# charger.net
KiCad netlist of a schematic drawn in Altium Designer
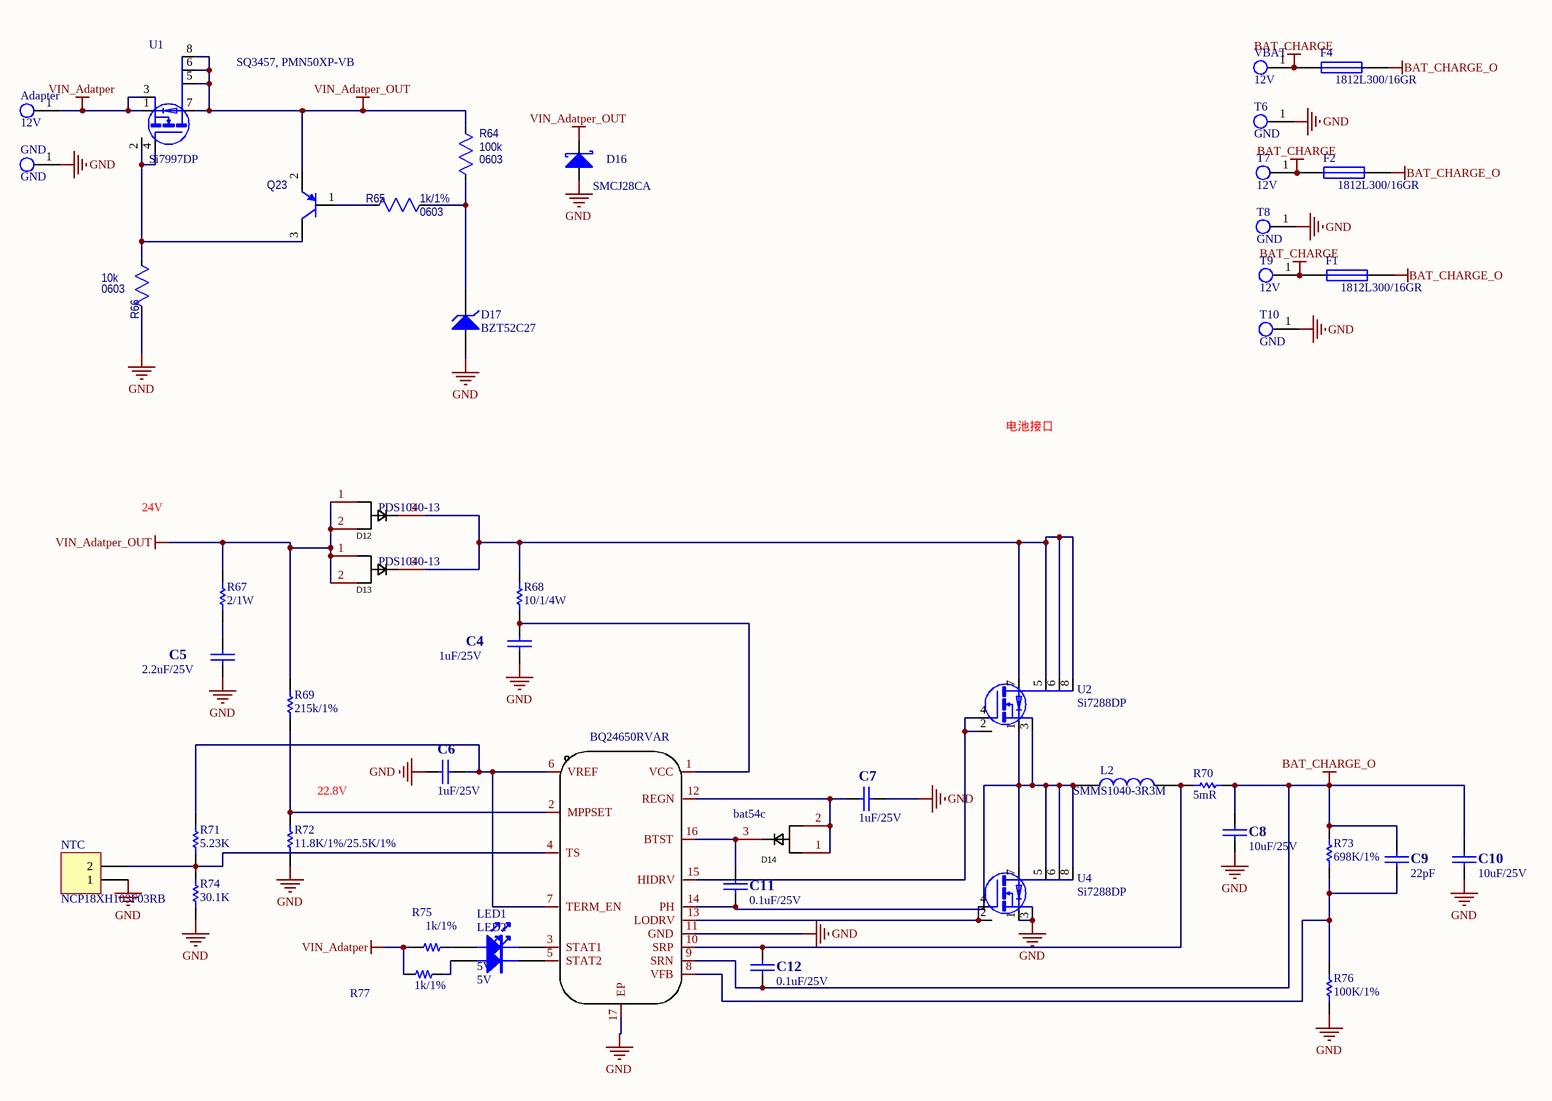
[diagram p0: charger.SchDoc]

(export (version "E")
  (design (tool "Eeschema 10.0.6"))
  (components
    (comp (ref "Adapter") (value "12V") (footprint "FIX-4.5") (libsource (lib "Schlib_20110825") (part "TP")))
    (comp (ref "C4")
      (value "1uF/25V")
      (footprint "0805C")
      (description "Capacitor")
      (libsource (lib "*") (part "CAP"))
    )
    (comp (ref "C5")
      (value "2.2uF/25V")
      (footprint "1210C")
      (description "Capacitor")
      (libsource (lib "*") (part "CAP"))
    )
    (comp (ref "C6")
      (value "1uF/25V")
      (footprint "0603C")
      (description "Capacitor")
      (libsource (lib "*") (part "CAP"))
    )
    (comp (ref "C7")
      (value "1uF/25V")
      (footprint "0603C")
      (description "Capacitor")
      (libsource (lib "*") (part "CAP"))
    )
    (comp (ref "C8")
      (value "10uF/25V")
      (footprint "0603C")
      (description "Capacitor")
      (libsource (lib "*") (part "CAP"))
    )
    (comp (ref "C9")
      (value "22pF")
      (footprint "0603C")
      (description "Capacitor")
      (libsource (lib "*") (part "CAP"))
    )
    (comp (ref "C10")
      (value "10uF/25V")
      (footprint "0603C")
      (description "Capacitor")
      (libsource (lib "*") (part "CAP"))
    )
    (comp (ref "C11")
      (value "0.1uF/25V")
      (footprint "0603C")
      (description "Capacitor")
      (libsource (lib "*") (part "CAP"))
    )
    (comp (ref "C12")
      (value "0.1uF/25V")
      (footprint "0603C")
      (description "Capacitor")
      (libsource (lib "*") (part "CAP"))
    )
    (comp (ref "D12")
      (value "PDS1040-13")
      (footprint "POWERDI-5_L5.4-W4.0-LS6.5-RD")
      (fields (field (name "MANUFACTURER") "DIODES(美台)"))
      (libsource (lib "Schlib_20110825") (part "PDS1040-13"))
    )
    (comp (ref "D13")
      (value "PDS1040-13")
      (footprint "POWERDI-5_L5.4-W4.0-LS6.5-RD")
      (fields (field (name "MANUFACTURER") "DIODES(美台)"))
      (libsource (lib "Schlib_20110825") (part "PDS1040-13"))
    )
    (comp (ref "D14")
      (value "bat54c")
      (footprint "sot23-3")
      (fields (field (name "MANUFACTURER") "DIODES(美台)") (field (name "MANUFACTURER PART") "PDS1040-13"))
      (libsource (lib "Schlib_20110825") (part "PDS1040-13"))
    )
    (comp (ref "D16")
      (value "SMCJ28CA")
      (footprint "SMC")
      (description "Schottky Diode")
      (libsource (lib "*") (part "DIODE S"))
    )
    (comp (ref "D17")
      (value "BZT52C27")
      (footprint "sod123")
      (libsource (lib "Bogen") (part "BZT52C12S-7-F"))
    )
    (comp (ref "F1")
      (value "1812L300/16GR")
      (footprint "1812-F")
      (description "Fuse")
      (fields (field (name "PUBLISHER") "Altium Limited"))
      (libsource (lib "Miscellaneous Devices") (part "Fuse 1"))
    )
    (comp (ref "F2")
      (value "1812L300/16GR")
      (footprint "1812-F")
      (description "Fuse")
      (fields (field (name "PUBLISHER") "Altium Limited"))
      (libsource (lib "Miscellaneous Devices") (part "Fuse 1"))
    )
    (comp (ref "F4")
      (value "1812L300/16GR")
      (footprint "1812-F")
      (description "Fuse")
      (fields (field (name "PUBLISHER") "Altium Limited"))
      (libsource (lib "Miscellaneous Devices") (part "Fuse 1"))
    )
    (comp (ref "GND") (value "GND") (footprint "FIX-4.5") (libsource (lib "Schlib_20110825") (part "TP")))
    (comp (ref "L2") (value "SMMS1040-3R3M") (footprint "MSS1038") (libsource (lib "*") (part "INDUCTOR")))
    (comp (ref "LED1") (value "5V") (footprint "0603LED") (libsource (lib "*") (part "LED")))
    (comp (ref "LED2") (value "5V") (footprint "0603LED") (libsource (lib "*") (part "LED")))
    (comp (ref "NTC")
      (value "NCP18XH103F03RB")
      (footprint "HDR1X2")
      (description "XH2.54 2P 立贴")
      (fields (field (name "PUBLISHER") "Altium Limited"))
      (libsource (lib "Miscellaneous Connectors") (part "Header 2"))
    )
    (comp (ref "Q23")
      (value "MMBT4403-7-F")
      (footprint "SOT23-3")
      (libsource (lib "Karl") (part "OEM_Diodes_MMBT4403"))
    )
    (comp (ref "R64")
      (value "100k")
      (footprint "RESC1608X055N_0603")
      (fields
        (field (name "PARTNUMBER") "RC0603FR-0716K9L")
        (field (name "TOLERANCE") "tol")
        (field (name "PACKAGE") "0603")
      )
      (libsource (lib "Karl") (part "Resistor_0603"))
    )
    (comp (ref "R65")
      (value "1k/1%")
      (footprint "RESC1608X055N_0603")
      (fields
        (field (name "PARTNUMBER") "RC0603FR-071KL")
        (field (name "TOLERANCE") "tol")
        (field (name "PACKAGE") "0603")
      )
      (libsource (lib "Karl") (part "Resistor_0603"))
    )
    (comp (ref "R66")
      (value "10k")
      (footprint "RESC1608X055N_0603")
      (fields
        (field (name "PARTNUMBER") "RC0603FR-071KL")
        (field (name "TOLERANCE") "tol")
        (field (name "PACKAGE") "0603")
      )
      (libsource (lib "Karl") (part "Resistor_0603"))
    )
    (comp (ref "R67")
      (value "2/1W")
      (footprint "2512R")
      (description "Resistor")
      (fields (field (name "PUBLISHER") "Altium Limited"))
      (libsource (lib "Miscellaneous Devices") (part "Res1"))
    )
    (comp (ref "R68")
      (value "10/1/4W")
      (footprint "1206R")
      (description "Resistor")
      (fields (field (name "PUBLISHER") "Altium Limited"))
      (libsource (lib "Miscellaneous Devices") (part "Res1"))
    )
    (comp (ref "R69")
      (value "215k/1%")
      (footprint "0603R")
      (description "Resistor")
      (fields (field (name "PUBLISHER") "Altium Limited"))
      (libsource (lib "Miscellaneous Devices") (part "Res1"))
    )
    (comp (ref "R70")
      (value "5mR")
      (footprint "2512R")
      (description "Resistor")
      (fields (field (name "PUBLISHER") "Altium Limited"))
      (libsource (lib "Miscellaneous Devices") (part "Res1"))
    )
    (comp (ref "R71")
      (value "5.23K")
      (footprint "0603R")
      (description "Resistor")
      (fields (field (name "PUBLISHER") "Altium Limited"))
      (libsource (lib "Miscellaneous Devices") (part "Res1"))
    )
    (comp (ref "R72")
      (value "11.8K/1%/25.5K/1%")
      (footprint "0603R")
      (description "Resistor")
      (fields (field (name "PUBLISHER") "Altium Limited"))
      (libsource (lib "Miscellaneous Devices") (part "Res1"))
    )
    (comp (ref "R73")
      (value "698K/1%")
      (footprint "0603R")
      (description "Resistor")
      (fields (field (name "PUBLISHER") "Altium Limited"))
      (libsource (lib "Miscellaneous Devices") (part "Res1"))
    )
    (comp (ref "R74")
      (value "30.1K")
      (footprint "0603R")
      (description "Resistor")
      (fields (field (name "PUBLISHER") "Altium Limited"))
      (libsource (lib "Miscellaneous Devices") (part "Res1"))
    )
    (comp (ref "R75") (value "1k/1%") (footprint "0603R") (libsource (lib "JRJ_1") (part "R")))
    (comp (ref "R76")
      (value "100K/1%")
      (footprint "0603R")
      (description "Resistor")
      (fields (field (name "PUBLISHER") "Altium Limited"))
      (libsource (lib "Miscellaneous Devices") (part "Res1"))
    )
    (comp (ref "R77") (value "1k/1%") (footprint "0603R") (libsource (lib "JRJ_1") (part "R")))
    (comp (ref "T6") (value "GND") (footprint "FIX-4.5") (libsource (lib "Schlib_20110825") (part "TP")))
    (comp (ref "T7") (value "12V") (footprint "FIX-4.5") (libsource (lib "Schlib_20110825") (part "TP")))
    (comp (ref "T8") (value "GND") (footprint "FIX-4.5") (libsource (lib "Schlib_20110825") (part "TP")))
    (comp (ref "T9") (value "12V") (footprint "FIX-4.5") (libsource (lib "Schlib_20110825") (part "TP")))
    (comp (ref "T10") (value "GND") (footprint "FIX-4.5") (libsource (lib "Schlib_20110825") (part "TP")))
    (comp (ref "U1")
      (value "Si7997DP")
      (footprint "PowerPAK SO-8")
      (description "Sia430DJ")
      (libsource (lib "Schlib_20110825") (part "Si7997DP"))
    )
    (comp (ref "U2")
      (value "Si7288DP")
      (footprint "PowerPAK SO-8")
      (description "Sia430DJ")
      (libsource (lib "Schlib_20110825") (part "Si7997DP"))
    )
    (comp (ref "U4")
      (value "Si7288DP")
      (footprint "PowerPAK SO-8")
      (description "Sia430DJ")
      (libsource (lib "Schlib_20110825") (part "Si7997DP"))
    )
    (comp (ref "U5")
      (value "BQ24650RVAR")
      (footprint "VQFN-16_L3.6-W3.6-P0.50-BL-EP")
      (fields (field (name "MANUFACTURER") "TI(德州仪器)"))
      (libsource (lib "Schlib_20110825") (part "BQ24650RVAR"))
    )
    (comp (ref "VBAT") (value "12V") (footprint "FIX-4.5") (libsource (lib "Schlib_20110825") (part "TP")))
  )
  (nets
    (net (code "1") (name "BAT_CHARGE") (class "Default")
      (node (ref "F1") (pin "1") (pinfunction "1_1") (pintype "passive"))
      (node (ref "F2") (pin "1") (pinfunction "1_1") (pintype "passive"))
      (node (ref "F4") (pin "1") (pinfunction "1_1") (pintype "passive"))
      (node (ref "T7") (pin "1") (pintype "passive"))
      (node (ref "T9") (pin "1") (pintype "passive"))
      (node (ref "VBAT") (pin "1") (pintype "passive"))
    )
    (net (code "2") (name "BAT_CHARGE_O") (class "Default")
      (node (ref "C10") (pin "2") (pinfunction "2_2") (pintype "passive"))
      (node (ref "C12") (pin "1") (pinfunction "1_1") (pintype "passive"))
      (node (ref "C8") (pin "2") (pinfunction "2_2") (pintype "passive"))
      (node (ref "C9") (pin "2") (pinfunction "2_2") (pintype "passive"))
      (node (ref "F1") (pin "2") (pinfunction "2_2") (pintype "passive"))
      (node (ref "F2") (pin "2") (pinfunction "2_2") (pintype "passive"))
      (node (ref "F4") (pin "2") (pinfunction "2_2") (pintype "passive"))
      (node (ref "R70") (pin "2") (pinfunction "2_2") (pintype "passive"))
      (node (ref "R73") (pin "1") (pinfunction "1_1") (pintype "passive"))
      (node (ref "U5") (pin "9") (pinfunction "SRN_9") (pintype "passive"))
    )
    (net (code "3") (name "GND") (class "Default")
      (node (ref "C10") (pin "1") (pinfunction "1_1") (pintype "passive"))
      (node (ref "C4") (pin "2") (pinfunction "2_2") (pintype "passive"))
      (node (ref "C5") (pin "2") (pinfunction "2_2") (pintype "passive"))
      (node (ref "C6") (pin "1") (pinfunction "1_1") (pintype "passive"))
      (node (ref "C7") (pin "2") (pinfunction "2_2") (pintype "passive"))
      (node (ref "C8") (pin "1") (pinfunction "1_1") (pintype "passive"))
      (node (ref "D16") (pin "1") (pinfunction "A_1") (pintype "passive"))
      (node (ref "D17") (pin "1") (pinfunction "A_1") (pintype "passive"))
      (node (ref "GND") (pin "1") (pintype "passive"))
      (node (ref "NTC") (pin "1") (pinfunction "1_1") (pintype "passive"))
      (node (ref "R66") (pin "2") (pinfunction "2_2") (pintype "passive"))
      (node (ref "R72") (pin "2") (pinfunction "2_2") (pintype "passive"))
      (node (ref "R74") (pin "2") (pinfunction "2_2") (pintype "passive"))
      (node (ref "R76") (pin "2") (pinfunction "2_2") (pintype "passive"))
      (node (ref "T10") (pin "1") (pintype "passive"))
      (node (ref "T6") (pin "1") (pintype "passive"))
      (node (ref "T8") (pin "1") (pintype "passive"))
      (node (ref "U4") (pin "1") (pinfunction "S_1") (pintype "passive"))
      (node (ref "U4") (pin "3") (pinfunction "S_3") (pintype "passive"))
      (node (ref "U5") (pin "11") (pinfunction "GND_11") (pintype "passive"))
      (node (ref "U5") (pin "17") (pinfunction "EP_17") (pintype "passive"))
    )
    (net (code "4") (name "Net-(C5-Pad1)") (class "Default")
      (node (ref "C5") (pin "1") (pinfunction "1_1") (pintype "passive"))
      (node (ref "R67") (pin "2") (pinfunction "2_2") (pintype "passive"))
    )
    (net (code "5") (name "Net-(D12-Pad3)") (class "Default")
      (node (ref "D12") (pin "3") (pinfunction "3_3") (pintype "passive"))
      (node (ref "D13") (pin "3") (pinfunction "3_3") (pintype "passive"))
      (node (ref "R68") (pin "1") (pinfunction "1_1") (pintype "passive"))
      (node (ref "U2") (pin "5") (pinfunction "D_5") (pintype "passive"))
      (node (ref "U2") (pin "6") (pinfunction "D_6") (pintype "passive"))
      (node (ref "U2") (pin "7") (pinfunction "D_7") (pintype "passive"))
      (node (ref "U2") (pin "8") (pinfunction "D_8") (pintype "passive"))
    )
    (net (code "6") (name "Net-(D14-LEFT)") (class "Default")
      (node (ref "C7") (pin "1") (pinfunction "1_1") (pintype "passive"))
      (node (ref "D14") (pin "1") (pinfunction "LEFT_1") (pintype "passive"))
      (node (ref "D14") (pin "2") (pinfunction "RIGHT_2") (pintype "passive"))
      (node (ref "U5") (pin "12") (pinfunction "REGN_12") (pintype "passive"))
    )
    (net (code "7") (name "Net-(D17-K)") (class "Default")
      (node (ref "D17") (pin "2") (pinfunction "K_2") (pintype "passive"))
      (node (ref "R64") (pin "1") (pinfunction "1_1") (pintype "passive"))
      (node (ref "R65") (pin "1") (pinfunction "1_1") (pintype "passive"))
    )
    (net (code "8") (name "Net-(LED1-Pad1)") (class "Default")
      (node (ref "LED1") (pin "1") (pinfunction "1_1") (pintype "passive"))
      (node (ref "R75") (pin "1") (pintype "passive"))
    )
    (net (code "9") (name "Net-(LED2-Pad1)") (class "Default")
      (node (ref "LED2") (pin "1") (pinfunction "1_1") (pintype "passive"))
      (node (ref "R77") (pin "1") (pintype "passive"))
    )
    (net (code "10") (name "Net-(Q23-B)") (class "Default")
      (node (ref "Q23") (pin "1") (pinfunction "B_1") (pintype "passive"))
      (node (ref "R65") (pin "2") (pinfunction "2_2") (pintype "passive"))
    )
    (net (code "11") (name "Net-(Q23-C)") (class "Default")
      (node (ref "Q23") (pin "3") (pinfunction "C_3") (pintype "passive"))
      (node (ref "R66") (pin "1") (pinfunction "1_1") (pintype "passive"))
      (node (ref "U1") (pin "2") (pinfunction "G_2") (pintype "passive"))
      (node (ref "U1") (pin "4") (pinfunction "G_4") (pintype "passive"))
    )
    (net (code "12") (name "Net-(U5-BTST)") (class "Default")
      (node (ref "C11") (pin "2") (pinfunction "2_2") (pintype "passive"))
      (node (ref "D14") (pin "3") (pinfunction "3_3") (pintype "passive"))
      (node (ref "U5") (pin "16") (pinfunction "BTST_16") (pintype "passive"))
    )
    (net (code "13") (name "Net-(U5-HIDRV)") (class "Default")
      (node (ref "U2") (pin "2") (pinfunction "G_2") (pintype "passive"))
      (node (ref "U2") (pin "4") (pinfunction "G_4") (pintype "passive"))
      (node (ref "U5") (pin "15") (pinfunction "HIDRV_15") (pintype "passive"))
    )
    (net (code "14") (name "Net-(U5-LODRV)") (class "Default")
      (node (ref "U4") (pin "2") (pinfunction "G_2") (pintype "passive"))
      (node (ref "U4") (pin "4") (pinfunction "G_4") (pintype "passive"))
      (node (ref "U5") (pin "13") (pinfunction "LODRV_13") (pintype "passive"))
    )
    (net (code "15") (name "Net-(U5-MPPSET)") (class "Default")
      (node (ref "R69") (pin "2") (pinfunction "2_2") (pintype "passive"))
      (node (ref "R72") (pin "1") (pinfunction "1_1") (pintype "passive"))
      (node (ref "U5") (pin "2") (pinfunction "MPPSET_2") (pintype "passive"))
    )
    (net (code "16") (name "Net-(U5-PH)") (class "Default")
      (node (ref "C11") (pin "1") (pinfunction "1_1") (pintype "passive"))
      (node (ref "L2") (pin "1") (pinfunction "1_1") (pintype "passive"))
      (node (ref "U2") (pin "1") (pinfunction "S_1") (pintype "passive"))
      (node (ref "U2") (pin "3") (pinfunction "S_3") (pintype "passive"))
      (node (ref "U4") (pin "5") (pinfunction "D_5") (pintype "passive"))
      (node (ref "U4") (pin "6") (pinfunction "D_6") (pintype "passive"))
      (node (ref "U4") (pin "7") (pinfunction "D_7") (pintype "passive"))
      (node (ref "U4") (pin "8") (pinfunction "D_8") (pintype "passive"))
      (node (ref "U5") (pin "14") (pinfunction "PH_14") (pintype "passive"))
    )
    (net (code "17") (name "Net-(U5-SRP)") (class "Default")
      (node (ref "C12") (pin "2") (pinfunction "2_2") (pintype "passive"))
      (node (ref "L2") (pin "2") (pinfunction "2_2") (pintype "passive"))
      (node (ref "R70") (pin "1") (pinfunction "1_1") (pintype "passive"))
      (node (ref "U5") (pin "10") (pinfunction "SRP_10") (pintype "passive"))
    )
    (net (code "18") (name "Net-(U5-STAT1)") (class "Default")
      (node (ref "LED1") (pin "2") (pinfunction "2_2") (pintype "passive"))
      (node (ref "U5") (pin "3") (pinfunction "STAT1_3") (pintype "passive"))
    )
    (net (code "19") (name "Net-(U5-STAT2)") (class "Default")
      (node (ref "LED2") (pin "2") (pinfunction "2_2") (pintype "passive"))
      (node (ref "U5") (pin "5") (pinfunction "STAT2_5") (pintype "passive"))
    )
    (net (code "20") (name "Net-(U5-TERM_EN)") (class "Default")
      (node (ref "C6") (pin "2") (pinfunction "2_2") (pintype "passive"))
      (node (ref "R71") (pin "1") (pinfunction "1_1") (pintype "passive"))
      (node (ref "U5") (pin "6") (pinfunction "VREF_6") (pintype "passive"))
      (node (ref "U5") (pin "7") (pinfunction "TERM_EN_7") (pintype "passive"))
    )
    (net (code "21") (name "Net-(U5-TS)") (class "Default")
      (node (ref "NTC") (pin "2") (pinfunction "2_2") (pintype "passive"))
      (node (ref "R71") (pin "2") (pinfunction "2_2") (pintype "passive"))
      (node (ref "R74") (pin "1") (pinfunction "1_1") (pintype "passive"))
      (node (ref "U5") (pin "4") (pinfunction "TS_4") (pintype "passive"))
    )
    (net (code "22") (name "Net-(U5-VCC)") (class "Default")
      (node (ref "C4") (pin "1") (pinfunction "1_1") (pintype "passive"))
      (node (ref "R68") (pin "2") (pinfunction "2_2") (pintype "passive"))
      (node (ref "U5") (pin "1") (pinfunction "VCC_1") (pintype "passive"))
    )
    (net (code "23") (name "Net-(U5-VFB)") (class "Default")
      (node (ref "C9") (pin "1") (pinfunction "1_1") (pintype "passive"))
      (node (ref "R73") (pin "2") (pinfunction "2_2") (pintype "passive"))
      (node (ref "R76") (pin "1") (pinfunction "1_1") (pintype "passive"))
      (node (ref "U5") (pin "8") (pinfunction "VFB_8") (pintype "passive"))
    )
    (net (code "24") (name "VIN_Adatper") (class "Default")
      (node (ref "Adapter") (pin "1") (pintype "passive"))
      (node (ref "R75") (pin "2") (pintype "passive"))
      (node (ref "R77") (pin "2") (pintype "passive"))
      (node (ref "U1") (pin "1") (pinfunction "S_1") (pintype "passive"))
      (node (ref "U1") (pin "3") (pinfunction "S_3") (pintype "passive"))
    )
    (net (code "25") (name "VIN_Adatper_OUT") (class "Default")
      (node (ref "D12") (pin "1") (pinfunction "LEFT_1") (pintype "passive"))
      (node (ref "D12") (pin "2") (pinfunction "RIGHT_2") (pintype "passive"))
      (node (ref "D13") (pin "1") (pinfunction "LEFT_1") (pintype "passive"))
      (node (ref "D13") (pin "2") (pinfunction "RIGHT_2") (pintype "passive"))
      (node (ref "D16") (pin "2") (pinfunction "K_2") (pintype "passive"))
      (node (ref "Q23") (pin "2") (pinfunction "E_2") (pintype "passive"))
      (node (ref "R64") (pin "2") (pinfunction "2_2") (pintype "passive"))
      (node (ref "R67") (pin "1") (pinfunction "1_1") (pintype "passive"))
      (node (ref "R69") (pin "1") (pinfunction "1_1") (pintype "passive"))
      (node (ref "U1") (pin "5") (pinfunction "D_5") (pintype "passive"))
      (node (ref "U1") (pin "6") (pinfunction "D_6") (pintype "passive"))
      (node (ref "U1") (pin "7") (pinfunction "D_7") (pintype "passive"))
      (node (ref "U1") (pin "8") (pinfunction "D_8") (pintype "passive"))
    )
  )
)
